# SCH_ESP32_PCB_2026-04-29.net
KiCad netlist of a schematic drawn in EasyEDA
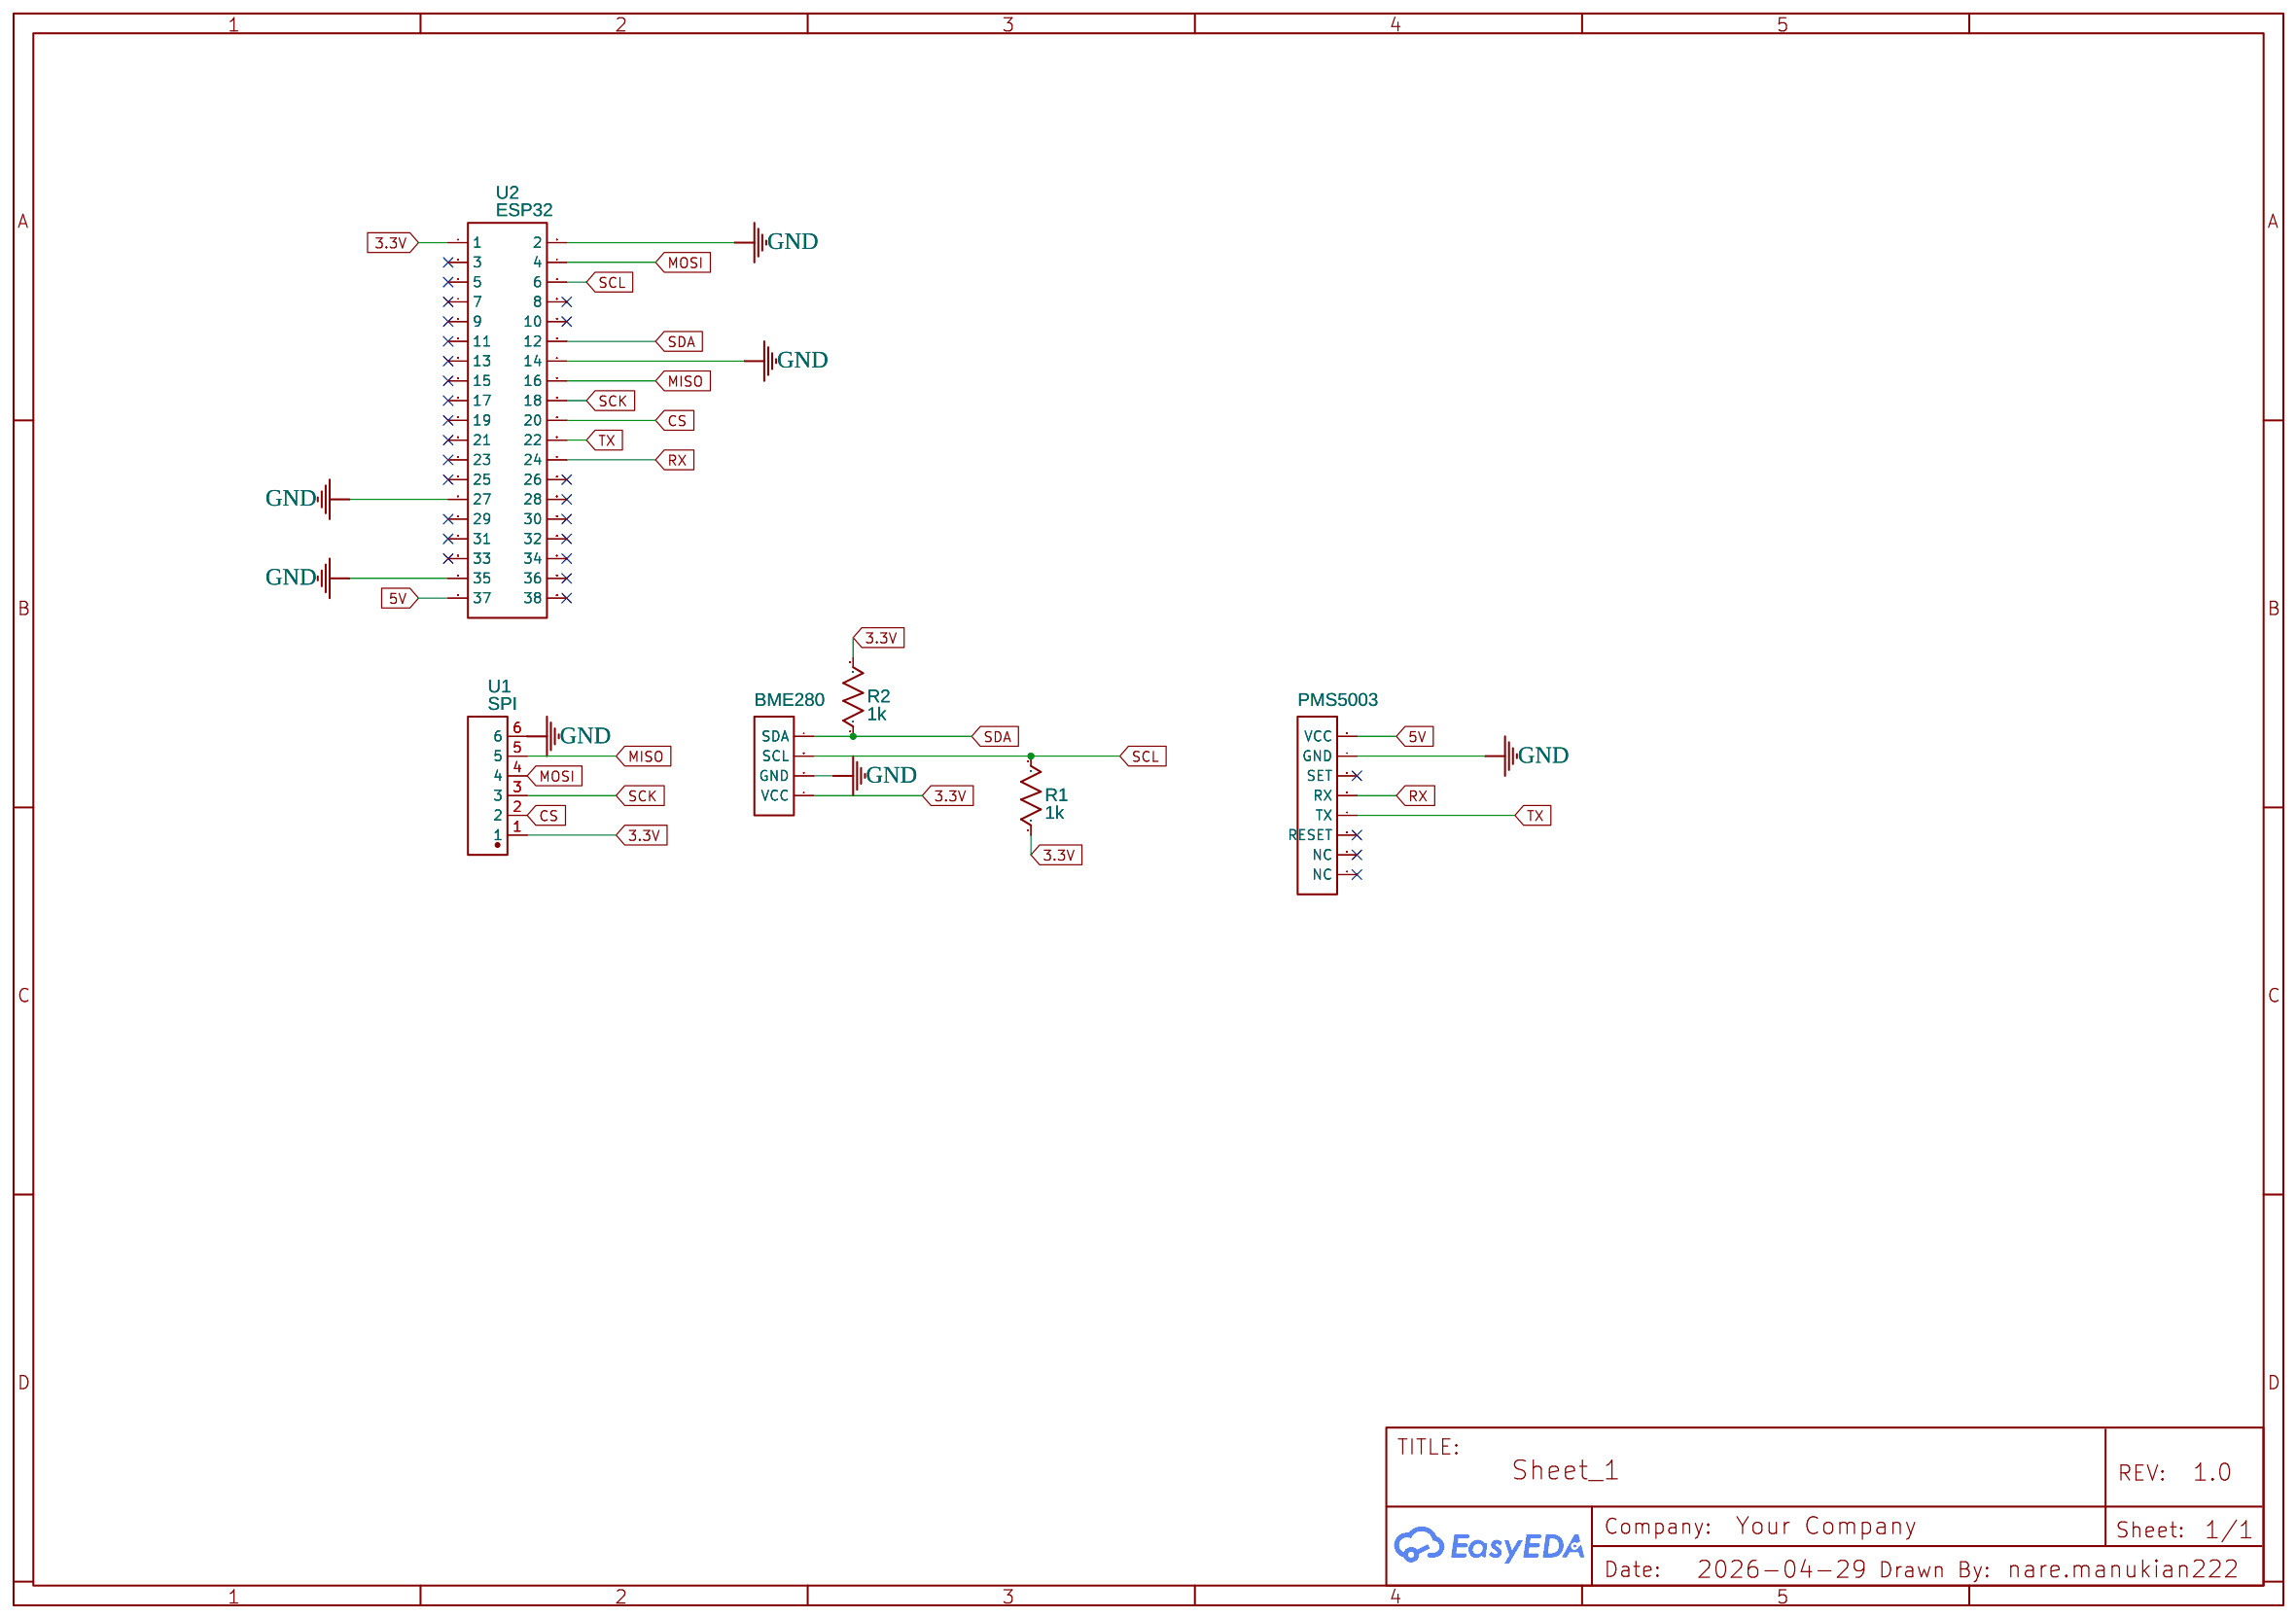
[diagram p0: schematic sheet]

(export (version "E")
  (design (tool "Eeschema 10.0.6"))
  (components
    (comp (ref "H1") (value "BME280") (libsource (lib "") (part "HDR-F-2.54_1x4")))
    (comp (ref "H2") (value "PMS5003") (libsource (lib "") (part "HDR-F-2.54_1x8")))
    (comp (ref "R1") (value "1k") (libsource (lib "") (part "R_AXIAL-0.4_US")))
    (comp (ref "R2") (value "1k") (libsource (lib "") (part "R_AXIAL-0.4_US")))
    (comp (ref "U1")
      (value "SPI")
      (fields
        (field (name "Manufacturer Part") "HX PM2.0-1x6P WC")
        (field (name "Manufacturer") "hanxia(韩下)")
      )
      (libsource (lib "") (part "HX PM2.0-1X6P WC"))
    )
    (comp (ref "U2") (value "ESP32") (libsource (lib "") (part "HDR-F-2.54_2x19")))
  )
  (nets
    (net (code "1") (name "3.3V") (class "Default")
      (node (ref "H1") (pin "1") (pinfunction "VCC_1") (pintype "unspecified"))
      (node (ref "R1") (pin "1") (pinfunction "1_1") (pintype "unspecified"))
      (node (ref "R2") (pin "2") (pinfunction "2_2") (pintype "unspecified"))
      (node (ref "U1") (pin "1") (pinfunction "1_1") (pintype "unspecified"))
      (node (ref "U2") (pin "1") (pinfunction "1_1") (pintype "input"))
    )
    (net (code "2") (name "5V") (class "Default")
      (node (ref "H2") (pin "8") (pinfunction "VCC_8") (pintype "unspecified"))
      (node (ref "U2") (pin "37") (pinfunction "37_37") (pintype "input"))
    )
    (net (code "3") (name "CS") (class "Default")
      (node (ref "U1") (pin "2") (pinfunction "2_2") (pintype "unspecified"))
      (node (ref "U2") (pin "20") (pinfunction "20_20") (pintype "input"))
    )
    (net (code "4") (name "GND") (class "Default")
      (node (ref "H1") (pin "2") (pinfunction "GND_2") (pintype "unspecified"))
      (node (ref "H2") (pin "7") (pinfunction "GND_7") (pintype "unspecified"))
      (node (ref "U1") (pin "6") (pinfunction "6_6") (pintype "unspecified"))
      (node (ref "U2") (pin "14") (pinfunction "14_14") (pintype "input"))
      (node (ref "U2") (pin "2") (pinfunction "2_2") (pintype "input"))
      (node (ref "U2") (pin "27") (pinfunction "27_27") (pintype "input"))
      (node (ref "U2") (pin "35") (pinfunction "35_35") (pintype "input"))
    )
    (net (code "5") (name "MISO") (class "Default")
      (node (ref "U1") (pin "5") (pinfunction "5_5") (pintype "unspecified"))
      (node (ref "U2") (pin "16") (pinfunction "16_16") (pintype "input"))
    )
    (net (code "6") (name "MOSI") (class "Default")
      (node (ref "U1") (pin "4") (pinfunction "4_4") (pintype "unspecified"))
      (node (ref "U2") (pin "4") (pinfunction "4_4") (pintype "input"))
    )
    (net (code "7") (name "RX") (class "Default")
      (node (ref "H2") (pin "5") (pinfunction "RX_5") (pintype "unspecified"))
      (node (ref "U2") (pin "24") (pinfunction "24_24") (pintype "input"))
    )
    (net (code "8") (name "SCK") (class "Default")
      (node (ref "U1") (pin "3") (pinfunction "3_3") (pintype "unspecified"))
      (node (ref "U2") (pin "18") (pinfunction "18_18") (pintype "input"))
    )
    (net (code "9") (name "SCL") (class "Default")
      (node (ref "H1") (pin "3") (pinfunction "SCL_3") (pintype "unspecified"))
      (node (ref "R1") (pin "2") (pinfunction "2_2") (pintype "unspecified"))
      (node (ref "U2") (pin "6") (pinfunction "6_6") (pintype "input"))
    )
    (net (code "10") (name "SDA") (class "Default")
      (node (ref "H1") (pin "4") (pinfunction "SDA_4") (pintype "unspecified"))
      (node (ref "R2") (pin "1") (pinfunction "1_1") (pintype "unspecified"))
      (node (ref "U2") (pin "12") (pinfunction "12_12") (pintype "input"))
    )
    (net (code "11") (name "TX") (class "Default")
      (node (ref "H2") (pin "4") (pinfunction "TX_4") (pintype "unspecified"))
      (node (ref "U2") (pin "22") (pinfunction "22_22") (pintype "input"))
    )
    (net (code "12") (name "unconnected-(H2-NC-Pad1)") (class "Default")
      (node (ref "H2") (pin "1") (pinfunction "NC_1") (pintype "unspecified+no_connect"))
    )
    (net (code "13") (name "unconnected-(H2-NC-Pad2)") (class "Default")
      (node (ref "H2") (pin "2") (pinfunction "NC_2") (pintype "unspecified+no_connect"))
    )
    (net (code "14") (name "unconnected-(H2-RESET-Pad3)") (class "Default")
      (node (ref "H2") (pin "3") (pinfunction "RESET_3") (pintype "unspecified+no_connect"))
    )
    (net (code "15") (name "unconnected-(H2-SET-Pad6)") (class "Default")
      (node (ref "H2") (pin "6") (pinfunction "SET_6") (pintype "unspecified+no_connect"))
    )
    (net (code "16") (name "unconnected-(U2-Pad3)") (class "Default")
      (node (ref "U2") (pin "3") (pinfunction "3_3") (pintype "input+no_connect"))
    )
    (net (code "17") (name "unconnected-(U2-Pad5)") (class "Default")
      (node (ref "U2") (pin "5") (pinfunction "5_5") (pintype "input+no_connect"))
    )
    (net (code "18") (name "unconnected-(U2-Pad7)") (class "Default")
      (node (ref "U2") (pin "7") (pinfunction "7_7") (pintype "input+no_connect"))
    )
    (net (code "19") (name "unconnected-(U2-Pad8)") (class "Default")
      (node (ref "U2") (pin "8") (pinfunction "8_8") (pintype "input+no_connect"))
    )
    (net (code "20") (name "unconnected-(U2-Pad9)") (class "Default")
      (node (ref "U2") (pin "9") (pinfunction "9_9") (pintype "input+no_connect"))
    )
    (net (code "21") (name "unconnected-(U2-Pad10)") (class "Default")
      (node (ref "U2") (pin "10") (pinfunction "10_10") (pintype "input+no_connect"))
    )
    (net (code "22") (name "unconnected-(U2-Pad11)") (class "Default")
      (node (ref "U2") (pin "11") (pinfunction "11_11") (pintype "input+no_connect"))
    )
    (net (code "23") (name "unconnected-(U2-Pad13)") (class "Default")
      (node (ref "U2") (pin "13") (pinfunction "13_13") (pintype "input+no_connect"))
    )
    (net (code "24") (name "unconnected-(U2-Pad15)") (class "Default")
      (node (ref "U2") (pin "15") (pinfunction "15_15") (pintype "input+no_connect"))
    )
    (net (code "25") (name "unconnected-(U2-Pad17)") (class "Default")
      (node (ref "U2") (pin "17") (pinfunction "17_17") (pintype "input+no_connect"))
    )
    (net (code "26") (name "unconnected-(U2-Pad19)") (class "Default")
      (node (ref "U2") (pin "19") (pinfunction "19_19") (pintype "input+no_connect"))
    )
    (net (code "27") (name "unconnected-(U2-Pad21)") (class "Default")
      (node (ref "U2") (pin "21") (pinfunction "21_21") (pintype "input+no_connect"))
    )
    (net (code "28") (name "unconnected-(U2-Pad23)") (class "Default")
      (node (ref "U2") (pin "23") (pinfunction "23_23") (pintype "input+no_connect"))
    )
    (net (code "29") (name "unconnected-(U2-Pad25)") (class "Default")
      (node (ref "U2") (pin "25") (pinfunction "25_25") (pintype "input+no_connect"))
    )
    (net (code "30") (name "unconnected-(U2-Pad26)") (class "Default")
      (node (ref "U2") (pin "26") (pinfunction "26_26") (pintype "input+no_connect"))
    )
    (net (code "31") (name "unconnected-(U2-Pad28)") (class "Default")
      (node (ref "U2") (pin "28") (pinfunction "28_28") (pintype "input+no_connect"))
    )
    (net (code "32") (name "unconnected-(U2-Pad29)") (class "Default")
      (node (ref "U2") (pin "29") (pinfunction "29_29") (pintype "input+no_connect"))
    )
    (net (code "33") (name "unconnected-(U2-Pad30)") (class "Default")
      (node (ref "U2") (pin "30") (pinfunction "30_30") (pintype "input+no_connect"))
    )
    (net (code "34") (name "unconnected-(U2-Pad31)") (class "Default")
      (node (ref "U2") (pin "31") (pinfunction "31_31") (pintype "input+no_connect"))
    )
    (net (code "35") (name "unconnected-(U2-Pad32)") (class "Default")
      (node (ref "U2") (pin "32") (pinfunction "32_32") (pintype "input+no_connect"))
    )
    (net (code "36") (name "unconnected-(U2-Pad33)") (class "Default")
      (node (ref "U2") (pin "33") (pinfunction "33_33") (pintype "input+no_connect"))
    )
    (net (code "37") (name "unconnected-(U2-Pad34)") (class "Default")
      (node (ref "U2") (pin "34") (pinfunction "34_34") (pintype "input+no_connect"))
    )
    (net (code "38") (name "unconnected-(U2-Pad36)") (class "Default")
      (node (ref "U2") (pin "36") (pinfunction "36_36") (pintype "input+no_connect"))
    )
    (net (code "39") (name "unconnected-(U2-Pad38)") (class "Default")
      (node (ref "U2") (pin "38") (pinfunction "38_38") (pintype "input+no_connect"))
    )
  )
)
